# OutputConnectors.net
KiCad netlist of a schematic drawn in Altium Designer
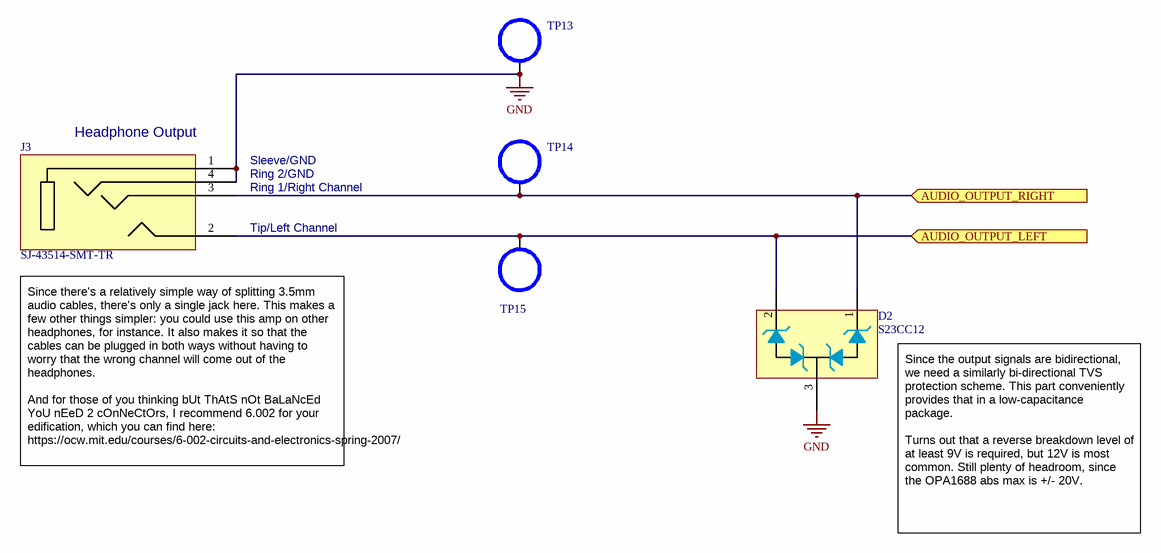
[diagram p0: OutputConnectors.SchDoc]

(export (version "E")
  (design (tool "Eeschema 10.0.6"))
  (components
    (comp (ref "D2")
      (value "S23CC12")
      (footprint "S23CC12 - SOT90P240X110-3M")
      (description "12V 2-CHANNEL LOW CAPACITANCE BI-DIRECTIONAL TVS ARRAY")
      (libsource (lib "Diodes") (part "S23CC12"))
    )
    (comp (ref "J3")
      (value "SJ-43514-SMT-TR")
      (footprint "SJ-43514-SMT-TR")
      (libsource (lib "Connectors") (part "SJ-43514-SMT-TR"))
    )
    (comp (ref "TP13")
      (value "TestPointHook")
      (footprint "S2751-46R")
      (description "Test point, SMT ring (micro-hook compatible)")
      (libsource (lib "PCBFeatures") (part "TestPointHook"))
    )
    (comp (ref "TP14")
      (value "TestPointHook")
      (footprint "S2751-46R")
      (description "Test point, SMT ring (micro-hook compatible)")
      (libsource (lib "PCBFeatures") (part "TestPointHook"))
    )
    (comp (ref "TP15")
      (value "TestPointHook")
      (footprint "S2751-46R")
      (description "Test point, SMT ring (micro-hook compatible)")
      (libsource (lib "PCBFeatures") (part "TestPointHook"))
    )
  )
  (nets
    (net (code "1") (name "/AUDIO_OUTPUT_LEFT") (class "Default")
      (node (ref "D2") (pin "2") (pinfunction "2_2") (pintype "passive"))
      (node (ref "J3") (pin "2") (pinfunction "2_2") (pintype "passive"))
      (node (ref "TP15") (pin "1") (pinfunction "1_1") (pintype "passive"))
    )
    (net (code "2") (name "/AUDIO_OUTPUT_RIGHT") (class "Default")
      (node (ref "D2") (pin "1") (pinfunction "1_1") (pintype "passive"))
      (node (ref "J3") (pin "3") (pinfunction "3_3") (pintype "passive"))
      (node (ref "TP14") (pin "1") (pinfunction "1_1") (pintype "passive"))
    )
    (net (code "3") (name "GND") (class "Default")
      (node (ref "D2") (pin "3") (pinfunction "3_3") (pintype "passive"))
      (node (ref "J3") (pin "1") (pinfunction "1_1") (pintype "passive"))
      (node (ref "J3") (pin "4") (pinfunction "4_4") (pintype "passive"))
      (node (ref "TP13") (pin "1") (pinfunction "1_1") (pintype "passive"))
    )
  )
)
